# MCU.net
KiCad netlist of a schematic drawn in Altium Designer
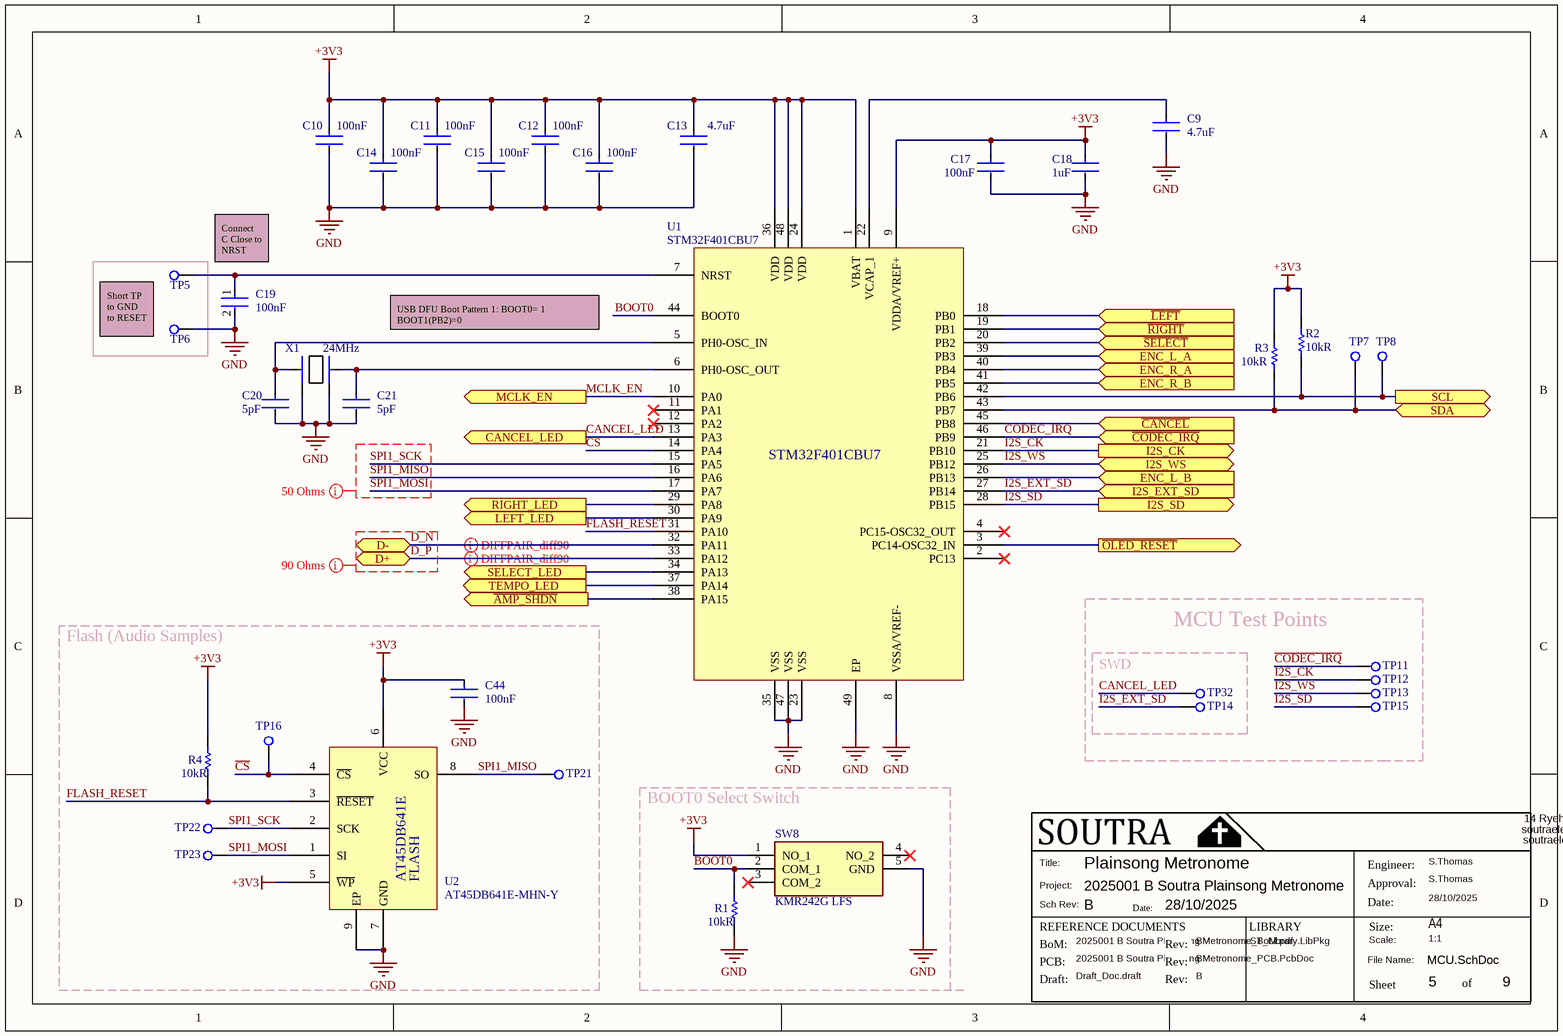
[diagram p0: MCU.SchDoc]

(export (version "E")
  (design (tool "Eeschema 10.0.6"))
  (components
    (comp (ref "C9")
      (value "4.7uF")
      (footprint "CC1206-IPC_A")
      (fields
        (field (name "MANUFACTURER") "Samsung")
        (field (name "MANUFACTURER PART NUMBER") "CL31B475KAHNNNE")
      )
      (libsource (lib "ST_Library") (part "CL31B475KAHNNNE"))
    )
    (comp (ref "C10")
      (value "100nF")
      (footprint "CAPC1005X06L")
      (fields
        (field (name "MANUFACTURER") "Walsin Technologies")
        (field (name "MANUFACTURER PART NUMBER") "0402X104M160CT")
        (field (name "ALTERNATIVE PART") "885012105016")
      )
      (libsource (lib "ST_Library") (part "0402X104M160CT"))
    )
    (comp (ref "C11")
      (value "100nF")
      (footprint "CAPC1005X06L")
      (fields
        (field (name "MANUFACTURER") "Walsin Technologies")
        (field (name "MANUFACTURER PART NUMBER") "0402X104M160CT")
        (field (name "ALTERNATIVE PART") "885012105016")
      )
      (libsource (lib "ST_Library") (part "0402X104M160CT"))
    )
    (comp (ref "C12")
      (value "100nF")
      (footprint "CAPC1005X06L")
      (fields
        (field (name "MANUFACTURER") "Walsin Technologies")
        (field (name "MANUFACTURER PART NUMBER") "0402X104M160CT")
        (field (name "ALTERNATIVE PART") "885012105016")
      )
      (libsource (lib "ST_Library") (part "0402X104M160CT"))
    )
    (comp (ref "C13")
      (value "4.7uF")
      (footprint "CC1206-IPC_A")
      (fields
        (field (name "MANUFACTURER") "Samsung")
        (field (name "MANUFACTURER PART NUMBER") "CL31B475KAHNNNE")
      )
      (libsource (lib "ST_Library") (part "CL31B475KAHNNNE"))
    )
    (comp (ref "C14")
      (value "100nF")
      (footprint "CAPC1005X06L")
      (fields
        (field (name "MANUFACTURER") "Walsin Technologies")
        (field (name "MANUFACTURER PART NUMBER") "0402X104M160CT")
        (field (name "ALTERNATIVE PART") "885012105016")
      )
      (libsource (lib "ST_Library") (part "0402X104M160CT"))
    )
    (comp (ref "C15")
      (value "100nF")
      (footprint "CAPC1005X06L")
      (fields
        (field (name "MANUFACTURER") "Walsin Technologies")
        (field (name "MANUFACTURER PART NUMBER") "0402X104M160CT")
        (field (name "ALTERNATIVE PART") "885012105016")
      )
      (libsource (lib "ST_Library") (part "0402X104M160CT"))
    )
    (comp (ref "C16")
      (value "100nF")
      (footprint "CAPC1005X06L")
      (fields
        (field (name "MANUFACTURER") "Walsin Technologies")
        (field (name "MANUFACTURER PART NUMBER") "0402X104M160CT")
        (field (name "ALTERNATIVE PART") "885012105016")
      )
      (libsource (lib "ST_Library") (part "0402X104M160CT"))
    )
    (comp (ref "C17")
      (value "100nF")
      (footprint "CAPC1005X06L")
      (fields
        (field (name "MANUFACTURER") "Walsin Technologies")
        (field (name "MANUFACTURER PART NUMBER") "0402X104M160CT")
        (field (name "ALTERNATIVE PART") "885012105016")
      )
      (libsource (lib "ST_Library") (part "0402X104M160CT"))
    )
    (comp (ref "C18")
      (value "1uF")
      (footprint "CAPC1005X06L")
      (fields
        (field (name "MANUFACTURER") "Yageo")
        (field (name "MANUFACTURER PART NUMBER") "CC0402KRX5R6BB105")
        (field (name "ALTERNATIVE PART") "0402ZD105KAT2A")
      )
      (libsource (lib "ST_Library") (part "CC0402KRX5R6BB105"))
    )
    (comp (ref "C19")
      (value "100nF")
      (footprint "CAPC1005X06L")
      (fields
        (field (name "MANUFACTURER") "Walsin Technologies")
        (field (name "MANUFACTURER PART NUMBER") "0402X104M160CT")
        (field (name "ALTERNATIVE PART") "885012105016")
      )
      (libsource (lib "") (part "0402X104M160CT_1"))
    )
    (comp (ref "C20")
      (value "5pF")
      (footprint "CAPC1005X06L")
      (fields
        (field (name "MANUFACTURER") "Yageo")
        (field (name "MANUFACTURER PART NUMBER") "CC0402CRNPO9BN5R0")
        (field (name "ALTERNATIVE PART") "GJM1555C1H5R0CB01D")
      )
      (libsource (lib "ST_Library") (part "CC0402CRNPO9BN5R0"))
    )
    (comp (ref "C21")
      (value "5pF")
      (footprint "CAPC1005X06L")
      (fields
        (field (name "MANUFACTURER") "Yageo")
        (field (name "MANUFACTURER PART NUMBER") "CC0402CRNPO9BN5R0")
        (field (name "ALTERNATIVE PART") "GJM1555C1H5R0CB01D")
      )
      (libsource (lib "ST_Library") (part "CC0402CRNPO9BN5R0"))
    )
    (comp (ref "C44")
      (value "100nF")
      (footprint "CAPC1005X06L")
      (fields
        (field (name "MANUFACTURER") "Walsin Technologies")
        (field (name "MANUFACTURER PART NUMBER") "0402X104M160CT")
        (field (name "ALTERNATIVE PART") "885012105016")
      )
      (libsource (lib "ST_Library") (part "0402X104M160CT"))
    )
    (comp (ref "R1")
      (value "10kR")
      (footprint "RESC_0805_2013X50X30LL20T20")
      (fields
        (field (name "MANUFACTURER") "Yageo")
        (field (name "MANUFACTURER PART NUMBER") "RC0805JR-0710KL")
        (field (name "TOLERANCE") "5%")
      )
      (libsource (lib "ST_Library") (part "RC0805JR-0710KL"))
    )
    (comp (ref "R2")
      (value "10kR")
      (footprint "RESC_0603_1608X06L")
      (fields
        (field (name "MANUFACTURER") "KOA Speer")
        (field (name "MANUFACTURER PART NUMBER") "RK73B1JTTD103J")
        (field (name "TOLERANCE") "5%")
      )
      (libsource (lib "ST_Library") (part "RK73B1JTTD103J"))
    )
    (comp (ref "R3")
      (value "10kR")
      (footprint "RESC_0603_1608X06L")
      (fields
        (field (name "MANUFACTURER") "KOA Speer")
        (field (name "MANUFACTURER PART NUMBER") "RK73B1JTTD103J")
        (field (name "TOLERANCE") "5%")
      )
      (libsource (lib "ST_Library") (part "RK73B1JTTD103J"))
    )
    (comp (ref "R4")
      (value "10kR")
      (footprint "RESC_0805_2013X50X30LL20T20")
      (fields
        (field (name "MANUFACTURER") "Yageo")
        (field (name "MANUFACTURER PART NUMBER") "RC0805JR-0710KL")
        (field (name "TOLERANCE") "5%")
      )
      (libsource (lib "ST_Library") (part "RC0805JR-0710KL"))
    )
    (comp (ref "SW8")
      (value "KMR242G LFS")
      (footprint "KMR242GLFS")
      (description "Switch Tactile N.O. SPST Round Button Gull Wing 0.05A 32VDC 1VA 200000Cycle 4N SMD T/R")
      (fields (field (name "MANUFACTURER") "C&K Components"))
      (libsource (lib "ST_Schematic-Library") (part "KMR242G LFS"))
    )
    (comp (ref "TP5")
      (value "TP_CIRCLE_R1")
      (footprint "TP_CIRCLE_R1")
      (description "Test Point, SMD, Circular, Radius = 1mm")
      (libsource (lib "ST_Library") (part "TP_CIRCLE_R1"))
    )
    (comp (ref "TP6")
      (value "TP_CIRCLE_R1")
      (footprint "TP_CIRCLE_R1")
      (description "Test Point, SMD, Circular, Radius = 1mm")
      (libsource (lib "ST_Library") (part "TP_CIRCLE_R1"))
    )
    (comp (ref "TP7")
      (value "TP_CIRCLE_R1")
      (footprint "TP_CIRCLE_R1")
      (description "Test Point, SMD, Circular, Radius = 1mm")
      (libsource (lib "ST_Library") (part "TP_CIRCLE_R1"))
    )
    (comp (ref "TP8")
      (value "TP_CIRCLE_R1")
      (footprint "TP_CIRCLE_R1")
      (description "Test Point, SMD, Circular, Radius = 1mm")
      (libsource (lib "ST_Library") (part "TP_CIRCLE_R1"))
    )
    (comp (ref "TP11")
      (value "TP_CIRCLE_R1")
      (footprint "TP_CIRCLE_R1")
      (description "Test Point, SMD, Circular, Radius = 1mm")
      (libsource (lib "ST_Library") (part "TP_CIRCLE_R1"))
    )
    (comp (ref "TP12")
      (value "TP_CIRCLE_R1")
      (footprint "TP_CIRCLE_R1")
      (description "Test Point, SMD, Circular, Radius = 1mm")
      (libsource (lib "ST_Library") (part "TP_CIRCLE_R1"))
    )
    (comp (ref "TP13")
      (value "TP_CIRCLE_R1")
      (footprint "TP_CIRCLE_R1")
      (description "Test Point, SMD, Circular, Radius = 1mm")
      (libsource (lib "ST_Library") (part "TP_CIRCLE_R1"))
    )
    (comp (ref "TP14")
      (value "TP_CIRCLE_R1")
      (footprint "TP_CIRCLE_R1")
      (description "Test Point, SMD, Circular, Radius = 1mm")
      (libsource (lib "ST_Library") (part "TP_CIRCLE_R1"))
    )
    (comp (ref "TP15")
      (value "TP_CIRCLE_R1")
      (footprint "TP_CIRCLE_R1")
      (description "Test Point, SMD, Circular, Radius = 1mm")
      (libsource (lib "ST_Library") (part "TP_CIRCLE_R1"))
    )
    (comp (ref "TP16")
      (value "TP_CIRCLE_R1")
      (footprint "TP_CIRCLE_R1")
      (description "Test Point, SMD, Circular, Radius = 1mm")
      (libsource (lib "ST_Library") (part "TP_CIRCLE_R1"))
    )
    (comp (ref "TP21")
      (value "TP_CIRCLE_R1")
      (footprint "TP_CIRCLE_R1")
      (description "Test Point, SMD, Circular, Radius = 1mm")
      (libsource (lib "ST_Library") (part "TP_CIRCLE_R1"))
    )
    (comp (ref "TP22")
      (value "TP_CIRCLE_R1")
      (footprint "TP_CIRCLE_R1")
      (description "Test Point, SMD, Circular, Radius = 1mm")
      (libsource (lib "ST_Library") (part "TP_CIRCLE_R1"))
    )
    (comp (ref "TP23")
      (value "TP_CIRCLE_R1")
      (footprint "TP_CIRCLE_R1")
      (description "Test Point, SMD, Circular, Radius = 1mm")
      (libsource (lib "ST_Library") (part "TP_CIRCLE_R1"))
    )
    (comp (ref "TP32")
      (value "TP_CIRCLE_R1")
      (footprint "TP_CIRCLE_R1")
      (description "Test Point, SMD, Circular, Radius = 1mm")
      (libsource (lib "ST_Library") (part "TP_CIRCLE_R1"))
    )
    (comp (ref "U1")
      (value "STM32F401CBU7")
      (footprint "UFQFPN50P700X700X60_HS-49L")
      (description "RISC Microcontroller, 32-Bit, FLASH, 84MHz, CMOS")
      (fields (field (name "MANUFACTURER") "STMicroelectronics"))
      (libsource (lib "ST_Library") (part "STM32F401CBU7"))
    )
    (comp (ref "U2")
      (value "AT45DB641E-MHN-Y")
      (footprint "QFN127P600X500X60_HS-9L")
      (description "Flash, 64MX1, PDSO8")
      (fields (field (name "MANUFACTURER") "Adesto Technologies"))
      (libsource (lib "ST_Library") (part "AT45DB641E-MHN-Y"))
    )
    (comp (ref "X1")
      (value "24MHz")
      (footprint "OSCSC1-85x1-55P2-55X2-05Y0-05_4MFR")
      (description "Parallel - Fundamental Quartz Crystal")
      (fields
        (field (name "MANUFACTURER") "Multicomp")
        (field (name "MANUFACTURER PART NUMBER") "MCSJK-7E-24.00-8-10-60-B-10")
      )
      (libsource (lib "ST_Library") (part "MCSJK-7E-24.00-8-10-60-B-10"))
    )
  )
  (nets
    (net (code "1") (name "+3V3") (class "Default")
      (node (ref "C10") (pin "1") (pinfunction "1_1") (pintype "passive"))
      (node (ref "C11") (pin "1") (pinfunction "1_1") (pintype "passive"))
      (node (ref "C12") (pin "1") (pinfunction "1_1") (pintype "passive"))
      (node (ref "C13") (pin "1") (pinfunction "1_1") (pintype "passive"))
      (node (ref "C14") (pin "1") (pinfunction "1_1") (pintype "passive"))
      (node (ref "C15") (pin "1") (pinfunction "1_1") (pintype "passive"))
      (node (ref "C16") (pin "1") (pinfunction "1_1") (pintype "passive"))
      (node (ref "C17") (pin "1") (pinfunction "1_1") (pintype "passive"))
      (node (ref "C18") (pin "1") (pinfunction "1_1") (pintype "passive"))
      (node (ref "C44") (pin "1") (pinfunction "1_1") (pintype "passive"))
      (node (ref "R2") (pin "2") (pinfunction "2_2") (pintype "passive"))
      (node (ref "R3") (pin "2") (pinfunction "2_2") (pintype "passive"))
      (node (ref "R4") (pin "2") (pinfunction "2_2") (pintype "passive"))
      (node (ref "SW8") (pin "1") (pinfunction "NO_1_1") (pintype "passive"))
      (node (ref "U1") (pin "1") (pinfunction "VBAT_1") (pintype "passive"))
      (node (ref "U1") (pin "24") (pinfunction "VDD_24") (pintype "passive"))
      (node (ref "U1") (pin "36") (pinfunction "VDD_36") (pintype "passive"))
      (node (ref "U1") (pin "48") (pinfunction "VDD_48") (pintype "passive"))
      (node (ref "U1") (pin "9") (pinfunction "VDDA/VREF+_9") (pintype "passive"))
      (node (ref "U2") (pin "5") (pinfunction "~{WP}_5") (pintype "passive"))
      (node (ref "U2") (pin "6") (pinfunction "VCC_6") (pintype "passive"))
    )
    (net (code "2") (name "/BOOT0") (class "Default")
      (node (ref "R1") (pin "2") (pinfunction "2_2") (pintype "passive"))
      (node (ref "SW8") (pin "2") (pinfunction "COM_1_2") (pintype "passive"))
      (node (ref "U1") (pin "44") (pinfunction "BOOT0_44") (pintype "passive"))
    )
    (net (code "3") (name "/CANCEL_LED") (class "Default")
      (node (ref "TP32") (pin "1") (pinfunction "1_1") (pintype "passive"))
      (node (ref "U1") (pin "13") (pinfunction "PA3_13") (pintype "passive"))
    )
    (net (code "4") (name "/D_N") (class "Default")
      (node (ref "U1") (pin "32") (pinfunction "PA11_32") (pintype "passive"))
    )
    (net (code "5") (name "/D_P") (class "Default")
      (node (ref "U1") (pin "33") (pinfunction "PA12_33") (pintype "passive"))
    )
    (net (code "6") (name "/ENC_L_A") (class "Default")
      (node (ref "U1") (pin "39") (pinfunction "PB3_39") (pintype "passive"))
    )
    (net (code "7") (name "/ENC_L_B") (class "Default")
      (node (ref "U1") (pin "26") (pinfunction "PB13_26") (pintype "passive"))
    )
    (net (code "8") (name "/ENC_R_A") (class "Default")
      (node (ref "U1") (pin "40") (pinfunction "PB4_40") (pintype "passive"))
    )
    (net (code "9") (name "/ENC_R_B") (class "Default")
      (node (ref "U1") (pin "41") (pinfunction "PB5_41") (pintype "passive"))
    )
    (net (code "10") (name "/FLASH_RESET") (class "Default")
      (node (ref "R4") (pin "1") (pinfunction "1_1") (pintype "passive"))
      (node (ref "U1") (pin "31") (pinfunction "PA10_31") (pintype "passive"))
      (node (ref "U2") (pin "3") (pinfunction "~{RESET}_3") (pintype "passive"))
    )
    (net (code "11") (name "/I2S_CK") (class "Default")
      (node (ref "TP12") (pin "1") (pinfunction "1_1") (pintype "passive"))
      (node (ref "U1") (pin "21") (pinfunction "PB10_21") (pintype "passive"))
    )
    (net (code "12") (name "/I2S_EXT_SD") (class "Default")
      (node (ref "TP14") (pin "1") (pinfunction "1_1") (pintype "passive"))
      (node (ref "U1") (pin "27") (pinfunction "PB14_27") (pintype "passive"))
    )
    (net (code "13") (name "/I2S_SD") (class "Default")
      (node (ref "TP15") (pin "1") (pinfunction "1_1") (pintype "passive"))
      (node (ref "U1") (pin "28") (pinfunction "PB15_28") (pintype "passive"))
    )
    (net (code "14") (name "/I2S_WS") (class "Default")
      (node (ref "TP13") (pin "1") (pinfunction "1_1") (pintype "passive"))
      (node (ref "U1") (pin "25") (pinfunction "PB12_25") (pintype "passive"))
    )
    (net (code "15") (name "/LEFT_LED") (class "Default")
      (node (ref "U1") (pin "30") (pinfunction "PA9_30") (pintype "passive"))
    )
    (net (code "16") (name "/MCLK_EN") (class "Default")
      (node (ref "U1") (pin "10") (pinfunction "PA0_10") (pintype "passive"))
    )
    (net (code "17") (name "/RIGHT_LED") (class "Default")
      (node (ref "U1") (pin "29") (pinfunction "PA8_29") (pintype "passive"))
    )
    (net (code "18") (name "/SCL") (class "Default")
      (node (ref "R2") (pin "1") (pinfunction "1_1") (pintype "passive"))
      (node (ref "TP8") (pin "1") (pinfunction "1_1") (pintype "passive"))
      (node (ref "U1") (pin "42") (pinfunction "PB6_42") (pintype "passive"))
    )
    (net (code "19") (name "/SDA") (class "Default")
      (node (ref "R3") (pin "1") (pinfunction "1_1") (pintype "passive"))
      (node (ref "TP7") (pin "1") (pinfunction "1_1") (pintype "passive"))
      (node (ref "U1") (pin "43") (pinfunction "PB7_43") (pintype "passive"))
    )
    (net (code "20") (name "/SELECT_LED") (class "Default")
      (node (ref "U1") (pin "34") (pinfunction "PA13_34") (pintype "passive"))
    )
    (net (code "21") (name "/SPI1_MISO") (class "Default")
      (node (ref "TP21") (pin "1") (pinfunction "1_1") (pintype "passive"))
      (node (ref "U1") (pin "16") (pinfunction "PA6_16") (pintype "passive"))
      (node (ref "U2") (pin "8") (pinfunction "SO_8") (pintype "passive"))
    )
    (net (code "22") (name "/SPI1_MOSI") (class "Default")
      (node (ref "TP23") (pin "1") (pinfunction "1_1") (pintype "passive"))
      (node (ref "U1") (pin "17") (pinfunction "PA7_17") (pintype "passive"))
      (node (ref "U2") (pin "1") (pinfunction "SI_1") (pintype "passive"))
    )
    (net (code "23") (name "/SPI1_SCK") (class "Default")
      (node (ref "TP22") (pin "1") (pinfunction "1_1") (pintype "passive"))
      (node (ref "U1") (pin "15") (pinfunction "PA5_15") (pintype "passive"))
      (node (ref "U2") (pin "2") (pinfunction "SCK_2") (pintype "passive"))
    )
    (net (code "24") (name "/TEMPO_LED") (class "Default")
      (node (ref "U1") (pin "37") (pinfunction "PA14_37") (pintype "passive"))
    )
    (net (code "25") (name "/~{AMP_SHDN}") (class "Default")
      (node (ref "U1") (pin "38") (pinfunction "PA15_38") (pintype "passive"))
    )
    (net (code "26") (name "/~{CANCEL}") (class "Default")
      (node (ref "U1") (pin "45") (pinfunction "PB8_45") (pintype "passive"))
    )
    (net (code "27") (name "/~{CODEC_IRQ}") (class "Default")
      (node (ref "TP11") (pin "1") (pinfunction "1_1") (pintype "passive"))
      (node (ref "U1") (pin "46") (pinfunction "PB9_46") (pintype "passive"))
    )
    (net (code "28") (name "/~{CS}") (class "Default")
      (node (ref "TP16") (pin "1") (pinfunction "1_1") (pintype "passive"))
      (node (ref "U1") (pin "14") (pinfunction "PA4_14") (pintype "passive"))
      (node (ref "U2") (pin "4") (pinfunction "~{CS}_4") (pintype "passive"))
    )
    (net (code "29") (name "/~{LEFT}") (class "Default")
      (node (ref "U1") (pin "18") (pinfunction "PB0_18") (pintype "passive"))
    )
    (net (code "30") (name "/~{OLED_RESET}") (class "Default")
      (node (ref "U1") (pin "3") (pinfunction "PC14-OSC32_IN_3") (pintype "passive"))
    )
    (net (code "31") (name "/~{RIGHT}") (class "Default")
      (node (ref "U1") (pin "19") (pinfunction "PB1_19") (pintype "passive"))
    )
    (net (code "32") (name "/~{SELECT}") (class "Default")
      (node (ref "U1") (pin "20") (pinfunction "PB2_20") (pintype "passive"))
    )
    (net (code "33") (name "GND") (class "Default")
      (node (ref "C10") (pin "2") (pinfunction "2_2") (pintype "passive"))
      (node (ref "C11") (pin "2") (pinfunction "2_2") (pintype "passive"))
      (node (ref "C12") (pin "2") (pinfunction "2_2") (pintype "passive"))
      (node (ref "C13") (pin "2") (pinfunction "2_2") (pintype "passive"))
      (node (ref "C14") (pin "2") (pinfunction "2_2") (pintype "passive"))
      (node (ref "C15") (pin "2") (pinfunction "2_2") (pintype "passive"))
      (node (ref "C16") (pin "2") (pinfunction "2_2") (pintype "passive"))
      (node (ref "C17") (pin "2") (pinfunction "2_2") (pintype "passive"))
      (node (ref "C18") (pin "2") (pinfunction "2_2") (pintype "passive"))
      (node (ref "C19") (pin "2") (pinfunction "2_2") (pintype "passive"))
      (node (ref "C20") (pin "2") (pinfunction "2_2") (pintype "passive"))
      (node (ref "C21") (pin "2") (pinfunction "2_2") (pintype "passive"))
      (node (ref "C44") (pin "2") (pinfunction "2_2") (pintype "passive"))
      (node (ref "C9") (pin "2") (pinfunction "2_2") (pintype "passive"))
      (node (ref "R1") (pin "1") (pinfunction "1_1") (pintype "passive"))
      (node (ref "SW8") (pin "5") (pinfunction "GND_5") (pintype "passive"))
      (node (ref "TP6") (pin "1") (pinfunction "1_1") (pintype "passive"))
      (node (ref "U1") (pin "23") (pinfunction "VSS_23") (pintype "passive"))
      (node (ref "U1") (pin "35") (pinfunction "VSS_35") (pintype "passive"))
      (node (ref "U1") (pin "47") (pinfunction "VSS_47") (pintype "passive"))
      (node (ref "U1") (pin "49") (pinfunction "EP_49") (pintype "passive"))
      (node (ref "U1") (pin "8") (pinfunction "VSSA/VREF-_8") (pintype "passive"))
      (node (ref "U2") (pin "7") (pinfunction "GND_7") (pintype "passive"))
      (node (ref "U2") (pin "9") (pinfunction "EP_9") (pintype "passive"))
      (node (ref "X1") (pin "2") (pinfunction "2_2") (pintype "passive"))
      (node (ref "X1") (pin "4") (pinfunction "4_4") (pintype "passive"))
    )
    (net (code "34") (name "Net-(U1-NRST)") (class "Default")
      (node (ref "C19") (pin "1") (pinfunction "1_1") (pintype "passive"))
      (node (ref "TP5") (pin "1") (pinfunction "1_1") (pintype "passive"))
      (node (ref "U1") (pin "7") (pinfunction "NRST_7") (pintype "passive"))
    )
    (net (code "35") (name "Net-(U1-PH0-OSC_IN)") (class "Default")
      (node (ref "C20") (pin "1") (pinfunction "1_1") (pintype "passive"))
      (node (ref "U1") (pin "5") (pinfunction "PH0-OSC_IN_5") (pintype "passive"))
      (node (ref "X1") (pin "1") (pinfunction "1_1") (pintype "passive"))
    )
    (net (code "36") (name "Net-(U1-PH0-OSC_OUT)") (class "Default")
      (node (ref "C21") (pin "1") (pinfunction "1_1") (pintype "passive"))
      (node (ref "U1") (pin "6") (pinfunction "PH0-OSC_OUT_6") (pintype "passive"))
      (node (ref "X1") (pin "3") (pinfunction "3_3") (pintype "passive"))
    )
    (net (code "37") (name "Net-(U1-VCAP_1)") (class "Default")
      (node (ref "C9") (pin "1") (pinfunction "1_1") (pintype "passive"))
      (node (ref "U1") (pin "22") (pinfunction "VCAP_1_22") (pintype "passive"))
    )
    (net (code "38") (name "unconnected-(SW8-COM_2-Pad3)") (class "Default")
      (node (ref "SW8") (pin "3") (pinfunction "COM_2_3") (pintype "passive+no_connect"))
    )
    (net (code "39") (name "unconnected-(SW8-NO_2-Pad4)") (class "Default")
      (node (ref "SW8") (pin "4") (pinfunction "NO_2_4") (pintype "passive+no_connect"))
    )
    (net (code "40") (name "unconnected-(U1-PA1-Pad11)") (class "Default")
      (node (ref "U1") (pin "11") (pinfunction "PA1_11") (pintype "passive+no_connect"))
    )
    (net (code "41") (name "unconnected-(U1-PA2-Pad12)") (class "Default")
      (node (ref "U1") (pin "12") (pinfunction "PA2_12") (pintype "passive+no_connect"))
    )
    (net (code "42") (name "unconnected-(U1-PC13-Pad2)") (class "Default")
      (node (ref "U1") (pin "2") (pinfunction "PC13_2") (pintype "passive+no_connect"))
    )
    (net (code "43") (name "unconnected-(U1-PC15-OSC32_OUT-Pad4)") (class "Default")
      (node (ref "U1") (pin "4") (pinfunction "PC15-OSC32_OUT_4") (pintype "passive+no_connect"))
    )
  )
)
